# Howland_Channel_1.net
KiCad netlist of a schematic drawn in Altium Designer
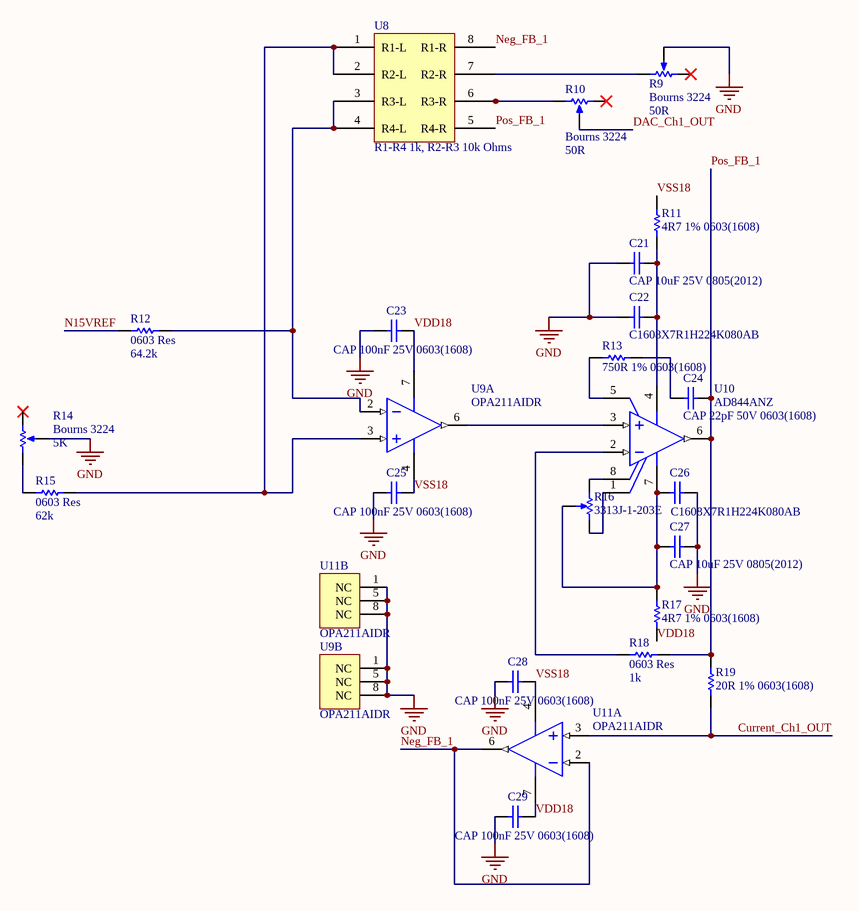
[diagram p0: Howland Channel 1.SchDoc]

(export (version "E")
  (design (tool "Eeschema 10.0.6"))
  (components
    (comp (ref "C21")
      (value "CAP 10uF 25V 0805(2012)")
      (footprint "CAPC0805(2012)145_N")
      (description "CAP 10uF 25V ±10% 0805 (2012 Metric) Thickness 1.45mm SMD")
      (fields (field (name "TOLERANCE") "Â±10%"))
      (libsource (lib "Altium Content Vault") (part "CAP"))
    )
    (comp (ref "C22")
      (value "C1608X7R1H224K080AB")
      (footprint "TDK-C1608-2_A_M")
      (description "Cap Ceramic, 0.22 uF, +/- 10%, -55 to 125 degC, 2-Pin SMD (0603), RoHS, Tape and Reel")
      (fields (field (name "MANUFACTURER") "TDK") (field (name "TOLERANCE") "±10%"))
      (libsource (lib "Altium Content Vault") (part "CAP-NP-2"))
    )
    (comp (ref "C23")
      (value "CAP 100nF 25V 0603(1608)")
      (footprint "CAPC0603(1608)100_N")
      (description "CAP 100nF 25V ±20% 0603 (1608 Metric) Thickness 1mm SMD")
      (fields (field (name "TOLERANCE") "Â±20%"))
      (libsource (lib "Altium Content Vault") (part "CAP"))
    )
    (comp (ref "C24")
      (value "CAP 22pF 50V 0603(1608)")
      (footprint "CAPC0603(1608)100_M")
      (description "CAP 22pF 50V ±2% 0603 (1608 Metric) Thickness 1mm SMD")
      (fields (field (name "TOLERANCE") "Â±2%"))
      (libsource (lib "Altium Content Vault") (part "CAP"))
    )
    (comp (ref "C25")
      (value "CAP 100nF 25V 0603(1608)")
      (footprint "CAPC0603(1608)100_N")
      (description "CAP 100nF 25V ±20% 0603 (1608 Metric) Thickness 1mm SMD")
      (fields (field (name "TOLERANCE") "Â±20%"))
      (libsource (lib "Altium Content Vault") (part "CAP"))
    )
    (comp (ref "C26")
      (value "C1608X7R1H224K080AB")
      (footprint "TDK-C1608-2_A_M")
      (description "Cap Ceramic, 0.22 uF, +/- 10%, -55 to 125 degC, 2-Pin SMD (0603), RoHS, Tape and Reel")
      (fields (field (name "MANUFACTURER") "TDK") (field (name "TOLERANCE") "±10%"))
      (libsource (lib "Altium Content Vault") (part "CAP-NP-2"))
    )
    (comp (ref "C27")
      (value "CAP 10uF 25V 0805(2012)")
      (footprint "CAPC0805(2012)145_N")
      (description "CAP 10uF 25V ±10% 0805 (2012 Metric) Thickness 1.45mm SMD")
      (fields (field (name "TOLERANCE") "Â±10%"))
      (libsource (lib "Altium Content Vault") (part "CAP"))
    )
    (comp (ref "C28")
      (value "CAP 100nF 25V 0603(1608)")
      (footprint "CAPC0603(1608)100_N")
      (description "CAP 100nF 25V ±20% 0603 (1608 Metric) Thickness 1mm SMD")
      (fields (field (name "TOLERANCE") "Â±20%"))
      (libsource (lib "Altium Content Vault") (part "CAP"))
    )
    (comp (ref "C29")
      (value "CAP 100nF 25V 0603(1608)")
      (footprint "CAPC0603(1608)100_N")
      (description "CAP 100nF 25V ±20% 0603 (1608 Metric) Thickness 1mm SMD")
      (fields (field (name "TOLERANCE") "Â±20%"))
      (libsource (lib "Altium Content Vault") (part "CAP"))
    )
    (comp (ref "R9")
      (value "Bourns 3224")
      (footprint "BOURNS 3224W")
      (description "Trimmer Potentiometer, Cermet, 3224-Series (Bourns)")
      (fields (field (name "ALTIUM_VALUE") "50R") (field (name "PUBLISHER") "Altium Limited"))
      (libsource (lib "ar5113_Altium_Library") (part "3224-Series Trimmer Potentiometer"))
    )
    (comp (ref "R10")
      (value "Bourns 3224")
      (footprint "BOURNS 3224W")
      (description "Trimmer Potentiometer, Cermet, 3224-Series (Bourns)")
      (fields (field (name "ALTIUM_VALUE") "50R") (field (name "PUBLISHER") "Altium Limited"))
      (libsource (lib "ar5113_Altium_Library") (part "3224-Series Trimmer Potentiometer"))
    )
    (comp (ref "R11")
      (value "4R7 1% 0603(1608)")
      (footprint "RESC0603(1608)_M")
      (description "4R7 0.1W 1% 0603 (1608 Metric)  SMD")
      (fields (field (name "POWER") "0.1 W") (field (name "TOLERANCE") "1 %"))
      (libsource (lib "Altium Content Vault") (part "RES"))
    )
    (comp (ref "R12")
      (value "0603 Res")
      (footprint "J1-0603")
      (description "Chip Resistor, 0603, 1%")
      (fields (field (name "ALTIUM_VALUE") "64.2k") (field (name "PUBLISHER") "Altium Limited"))
      (libsource (lib "Miscellaneous Devices") (part "Res1"))
    )
    (comp (ref "R13")
      (value "750R 1% 0603(1608)")
      (footprint "RESC0603(1608)_L")
      (description "750R 0.1W 1% 0603 (1608 Metric)  SMD")
      (fields (field (name "TOLERANCE") "1 %") (field (name "POWER") "0.1 W"))
      (libsource (lib "Altium Content Vault") (part "RES"))
    )
    (comp (ref "R14")
      (value "Bourns 3224")
      (footprint "BOURNS 3224W")
      (description "Trimmer Potentiometer, Cermet, 3224-Series (Bourns)")
      (fields (field (name "ALTIUM_VALUE") "5K") (field (name "PUBLISHER") "Altium Limited"))
      (libsource (lib "ar5113_Altium_Library") (part "3224-Series Trimmer Potentiometer"))
    )
    (comp (ref "R15")
      (value "0603 Res")
      (footprint "J1-0603")
      (description "Chip Resistor, 0603, 1%")
      (fields (field (name "ALTIUM_VALUE") "62k") (field (name "PUBLISHER") "Altium Limited"))
      (libsource (lib "Miscellaneous Devices") (part "Res1"))
    )
    (comp (ref "R16")
      (value "3313J-1-203E")
      (footprint "BOUR-3313J-1_V")
      (fields (field (name "MANUFACTURER") "Bourns") (field (name "TOLERANCE") "±20%"))
      (libsource (lib "Altium Content Vault") (part "RES-ADJ-3_A"))
    )
    (comp (ref "R17")
      (value "4R7 1% 0603(1608)")
      (footprint "RESC0603(1608)_M")
      (description "4R7 0.1W 1% 0603 (1608 Metric)  SMD")
      (fields (field (name "POWER") "0.1 W") (field (name "TOLERANCE") "1 %"))
      (libsource (lib "Altium Content Vault") (part "RES"))
    )
    (comp (ref "R18")
      (value "0603 Res")
      (footprint "J1-0603")
      (description "Chip Resistor, 0603, 1%")
      (fields (field (name "ALTIUM_VALUE") "1k") (field (name "PUBLISHER") "Altium Limited"))
      (libsource (lib "Miscellaneous Devices") (part "Res1"))
    )
    (comp (ref "R19")
      (value "20R 1% 0603(1608)")
      (footprint "RESC0603(1608)_M")
      (description "20R 0.1W 1% 0603 (1608 Metric)  SMD")
      (fields (field (name "TOLERANCE") "1 %") (field (name "POWER") "0.1 W"))
      (libsource (lib "Altium Content Vault") (part "RES"))
    )
    (comp (ref "U8")
      (value "R1-R4 1k, R2-R3 10k Ohms")
      (footprint "0612 (4x0603)")
      (description "Matched Resistor Network, Isolated, multi-0603 package, Abs Tol 0.1%, Rel Tol 0.05%")
      (libsource (lib "ar5113_Altium_Library") (part "VISHAY ACAS"))
    )
    (comp (ref "U9")
      (value "OPA211AIDR")
      (footprint "TI-D8_L")
      (fields (field (name "MANUFACTURER") "Texas Instruments"))
      (libsource (lib "Altium Content Vault") (part "TI-OPA-8_1"))
    )
    (comp (ref "U10")
      (value "AD844ANZ")
      (footprint "ADI-N-8")
      (fields (field (name "GENERIC PART NUMBER") "AD844") (field (name "MANUFACTURER") "Analog Devices"))
      (libsource (lib "Altium Content Vault") (part "ADI-AD844-N-8"))
    )
    (comp (ref "U11")
      (value "OPA211AIDR")
      (footprint "TI-D8_L")
      (fields (field (name "MANUFACTURER") "Texas Instruments"))
      (libsource (lib "Altium Content Vault") (part "TI-OPA-8_1"))
    )
  )
  (nets
    (net (code "1") (name "/Current_Ch1_OUT") (class "Default")
      (node (ref "R19") (pin "1") (pinfunction "1_1") (pintype "passive"))
      (node (ref "U11") (pin "3") (pinfunction "IN+_3") (pintype "input"))
    )
    (net (code "2") (name "/DAC_Ch1_OUT") (class "Default")
      (node (ref "R10") (pin "2") (pinfunction "TAP_2") (pintype "passive"))
    )
    (net (code "3") (name "/N15VREF") (class "Default")
      (node (ref "R12") (pin "2") (pinfunction "2_2") (pintype "passive"))
    )
    (net (code "4") (name "/Neg_FB_1") (class "Default")
      (node (ref "U11") (pin "2") (pinfunction "IN-_2") (pintype "input"))
      (node (ref "U11") (pin "6") (pinfunction "OUT_6") (pintype "output"))
      (node (ref "U8") (pin "8") (pinfunction "R1-R_8") (pintype "passive"))
    )
    (net (code "5") (name "/Pos_FB_1") (class "Default")
      (node (ref "C24") (pin "2") (pinfunction "2_2") (pintype "passive"))
      (node (ref "R18") (pin "1") (pinfunction "1_1") (pintype "passive"))
      (node (ref "R19") (pin "2") (pinfunction "2_2") (pintype "passive"))
      (node (ref "U10") (pin "6") (pinfunction "OUTPUT_6") (pintype "output"))
      (node (ref "U8") (pin "5") (pinfunction "R4-R_5") (pintype "passive"))
    )
    (net (code "6") (name "/VDD18") (class "Default")
      (node (ref "C23") (pin "2") (pinfunction "2_2") (pintype "passive"))
      (node (ref "C29") (pin "2") (pinfunction "2_2") (pintype "passive"))
      (node (ref "R17") (pin "1") (pinfunction "1_1") (pintype "passive"))
      (node (ref "U11") (pin "7") (pinfunction "V+_7") (pintype "power_in"))
      (node (ref "U9") (pin "7") (pinfunction "V+_7") (pintype "power_in"))
    )
    (net (code "7") (name "/VSS18") (class "Default")
      (node (ref "C25") (pin "2") (pinfunction "2_2") (pintype "passive"))
      (node (ref "C28") (pin "2") (pinfunction "2_2") (pintype "passive"))
      (node (ref "R11") (pin "2") (pinfunction "2_2") (pintype "passive"))
      (node (ref "U11") (pin "4") (pinfunction "V-_4") (pintype "power_in"))
      (node (ref "U9") (pin "4") (pinfunction "V-_4") (pintype "power_in"))
    )
    (net (code "8") (name "GND") (class "Default")
      (node (ref "C21") (pin "1") (pinfunction "1_1") (pintype "passive"))
      (node (ref "C22") (pin "1") (pinfunction "1_1") (pintype "passive"))
      (node (ref "C23") (pin "1") (pinfunction "1_1") (pintype "passive"))
      (node (ref "C25") (pin "1") (pinfunction "1_1") (pintype "passive"))
      (node (ref "C26") (pin "2") (pinfunction "2_2") (pintype "passive"))
      (node (ref "C27") (pin "2") (pinfunction "2_2") (pintype "passive"))
      (node (ref "C28") (pin "1") (pinfunction "1_1") (pintype "passive"))
      (node (ref "C29") (pin "1") (pinfunction "1_1") (pintype "passive"))
      (node (ref "R14") (pin "2") (pinfunction "TAP_2") (pintype "passive"))
      (node (ref "R9") (pin "2") (pinfunction "TAP_2") (pintype "passive"))
      (node (ref "U11") (pin "1") (pinfunction "NC_1") (pintype "passive"))
      (node (ref "U11") (pin "5") (pinfunction "NC_5") (pintype "passive"))
      (node (ref "U11") (pin "8") (pinfunction "NC_8") (pintype "passive"))
      (node (ref "U9") (pin "1") (pinfunction "NC_1") (pintype "passive"))
      (node (ref "U9") (pin "5") (pinfunction "NC_5") (pintype "passive"))
      (node (ref "U9") (pin "8") (pinfunction "NC_8") (pintype "passive"))
    )
    (net (code "9") (name "Net-(C24-Pad1)") (class "Default")
      (node (ref "C24") (pin "1") (pinfunction "1_1") (pintype "passive"))
      (node (ref "R13") (pin "2") (pinfunction "2_2") (pintype "passive"))
    )
    (net (code "10") (name "Net-(R9-BOT)") (class "Default")
      (node (ref "R9") (pin "3") (pinfunction "BOT_3") (pintype "passive"))
      (node (ref "U8") (pin "7") (pinfunction "R2-R_7") (pintype "passive"))
    )
    (net (code "11") (name "Net-(R10-TOP)") (class "Default")
      (node (ref "R10") (pin "1") (pinfunction "TOP_1") (pintype "passive"))
      (node (ref "U8") (pin "6") (pinfunction "R3-R_6") (pintype "passive"))
    )
    (net (code "12") (name "Net-(R14-TOP)") (class "Default")
      (node (ref "R14") (pin "1") (pinfunction "TOP_1") (pintype "passive"))
      (node (ref "R15") (pin "2") (pinfunction "2_2") (pintype "passive"))
    )
    (net (code "13") (name "Net-(R16-Pad1)") (class "Default")
      (node (ref "R16") (pin "1") (pinfunction "1_1") (pintype "passive"))
      (node (ref "U10") (pin "8") (pinfunction "NULL_8") (pintype "passive"))
    )
    (net (code "14") (name "Net-(R16-Pad3)") (class "Default")
      (node (ref "R16") (pin "3") (pinfunction "3_3") (pintype "passive"))
      (node (ref "U10") (pin "1") (pinfunction "NULL_1") (pintype "passive"))
    )
    (net (code "15") (name "Net-(U8-R1-L)") (class "Default")
      (node (ref "R15") (pin "1") (pinfunction "1_1") (pintype "passive"))
      (node (ref "U8") (pin "1") (pinfunction "R1-L_1") (pintype "passive"))
      (node (ref "U8") (pin "2") (pinfunction "R2-L_2") (pintype "passive"))
      (node (ref "U9") (pin "3") (pinfunction "IN+_3") (pintype "input"))
    )
    (net (code "16") (name "Net-(U8-R3-L)") (class "Default")
      (node (ref "R12") (pin "1") (pinfunction "1_1") (pintype "passive"))
      (node (ref "U8") (pin "3") (pinfunction "R3-L_3") (pintype "passive"))
      (node (ref "U8") (pin "4") (pinfunction "R4-L_4") (pintype "passive"))
      (node (ref "U9") (pin "2") (pinfunction "IN-_2") (pintype "input"))
    )
    (net (code "17") (name "Net-(U10-+IN)") (class "Default")
      (node (ref "U10") (pin "3") (pinfunction "+IN_3") (pintype "input"))
      (node (ref "U9") (pin "6") (pinfunction "OUT_6") (pintype "output"))
    )
    (net (code "18") (name "Net-(U10-+VS)") (class "Default")
      (node (ref "C26") (pin "1") (pinfunction "1_1") (pintype "passive"))
      (node (ref "C27") (pin "1") (pinfunction "1_1") (pintype "passive"))
      (node (ref "R16") (pin "2") (pinfunction "2_2") (pintype "passive"))
      (node (ref "R17") (pin "2") (pinfunction "2_2") (pintype "passive"))
      (node (ref "U10") (pin "7") (pinfunction "+VS_7") (pintype "power_in"))
    )
    (net (code "19") (name "Net-(U10--IN)") (class "Default")
      (node (ref "R18") (pin "2") (pinfunction "2_2") (pintype "passive"))
      (node (ref "U10") (pin "2") (pinfunction "-IN_2") (pintype "input"))
    )
    (net (code "20") (name "Net-(U10--VS)") (class "Default")
      (node (ref "C21") (pin "2") (pinfunction "2_2") (pintype "passive"))
      (node (ref "C22") (pin "2") (pinfunction "2_2") (pintype "passive"))
      (node (ref "R11") (pin "1") (pinfunction "1_1") (pintype "passive"))
      (node (ref "U10") (pin "4") (pinfunction "-VS_4") (pintype "power_in"))
    )
    (net (code "21") (name "Net-(U10-TZ)") (class "Default")
      (node (ref "R13") (pin "1") (pinfunction "1_1") (pintype "passive"))
      (node (ref "U10") (pin "5") (pinfunction "TZ_5") (pintype "passive"))
    )
    (net (code "22") (name "unconnected-(R9-TOP-Pad1)") (class "Default")
      (node (ref "R9") (pin "1") (pinfunction "TOP_1") (pintype "passive+no_connect"))
    )
    (net (code "23") (name "unconnected-(R10-BOT-Pad3)") (class "Default")
      (node (ref "R10") (pin "3") (pinfunction "BOT_3") (pintype "passive+no_connect"))
    )
    (net (code "24") (name "unconnected-(R14-BOT-Pad3)") (class "Default")
      (node (ref "R14") (pin "3") (pinfunction "BOT_3") (pintype "passive+no_connect"))
    )
  )
)
